# design.net
KiCad netlist of a schematic drawn in Altium Designer
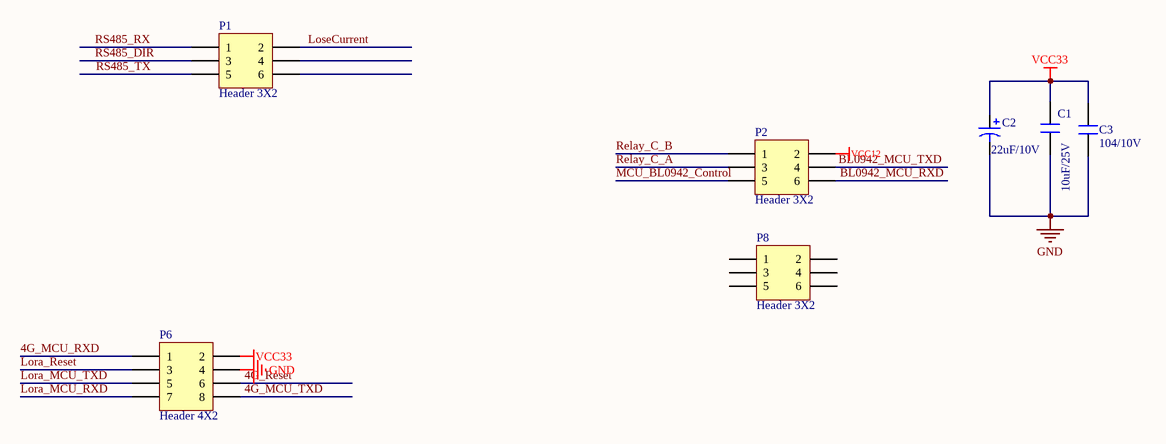
[diagram p0: 连接.SchDoc]

(export (version "E")
  (design (tool "Eeschema 10.0.6"))
  (components
    (comp (ref "C1") (value "10uF/25V") (footprint "0603R") (libsource (lib "ES_Schematic") (part "CAP")))
    (comp (ref "C2")
      (value "22uF/10V")
      (footprint "0805R")
      (description "Polarized Capacitor (Radial)")
      (fields (field (name "PUBLISHER") "Altium Limited"))
      (libsource (lib "Miscellaneous Devices") (part "Cap Pol1"))
    )
    (comp (ref "C3") (value "104/10V") (footprint "0603R") (libsource (lib "ES_Schematic") (part "CAP_1")))
    (comp (ref "P1")
      (value "Header 3X2")
      (footprint "CONN-SMD_5BME8-08872-203-W0")
      (description "Header, 3-Pin, Dual row")
      (fields (field (name "PUBLISHER") "Altium Limited"))
      (libsource (lib "Miscellaneous Connectors") (part "Header 3X2"))
    )
    (comp (ref "P2")
      (value "Header 3X2")
      (footprint "CONN-SMD_5BME8-08872-203-W0")
      (description "Header, 3-Pin, Dual row")
      (fields (field (name "PUBLISHER") "Altium Limited"))
      (libsource (lib "Miscellaneous Connectors") (part "Header 3X2"))
    )
    (comp (ref "P6")
      (value "Header 4X2")
      (footprint "CONN-SMD_5BME8-08872-204-W0")
      (description "Header, 4-Pin, Dual row")
      (fields (field (name "PUBLISHER") "Altium Limited"))
      (libsource (lib "Miscellaneous Connectors") (part "Header 4X2"))
    )
    (comp (ref "P8")
      (value "Header 3X2")
      (footprint "CONN-SMD_5BME8-08872-203-W0")
      (description "Header, 3-Pin, Dual row")
      (fields (field (name "PUBLISHER") "Altium Limited"))
      (libsource (lib "Miscellaneous Connectors") (part "Header 3X2"))
    )
  )
  (nets
    (net (code "1") (name "/4G_MCU_RXD") (class "Default")
      (node (ref "P6") (pin "1") (pinfunction "1_1") (pintype "passive"))
    )
    (net (code "2") (name "/4G_MCU_TXD") (class "Default")
      (node (ref "P6") (pin "8") (pinfunction "8_8") (pintype "passive"))
    )
    (net (code "3") (name "/4G_Reset") (class "Default")
      (node (ref "P6") (pin "6") (pinfunction "6_6") (pintype "passive"))
    )
    (net (code "4") (name "/BL0942_MCU_RXD") (class "Default")
      (node (ref "P2") (pin "6") (pinfunction "6_6") (pintype "passive"))
    )
    (net (code "5") (name "/BL0942_MCU_TXD") (class "Default")
      (node (ref "P2") (pin "4") (pinfunction "4_4") (pintype "passive"))
    )
    (net (code "6") (name "/Lora_MCU_RXD") (class "Default")
      (node (ref "P6") (pin "7") (pinfunction "7_7") (pintype "passive"))
    )
    (net (code "7") (name "/Lora_MCU_TXD") (class "Default")
      (node (ref "P6") (pin "5") (pinfunction "5_5") (pintype "passive"))
    )
    (net (code "8") (name "/Lora_Reset") (class "Default")
      (node (ref "P6") (pin "3") (pinfunction "3_3") (pintype "passive"))
    )
    (net (code "9") (name "/LoseCurrent") (class "Default")
      (node (ref "P1") (pin "2") (pinfunction "2_2") (pintype "passive"))
    )
    (net (code "10") (name "/MCU_BL0942_Control") (class "Default")
      (node (ref "P2") (pin "5") (pinfunction "5_5") (pintype "passive"))
    )
    (net (code "11") (name "/RS485_DIR") (class "Default")
      (node (ref "P1") (pin "3") (pinfunction "3_3") (pintype "passive"))
    )
    (net (code "12") (name "/RS485_RX") (class "Default")
      (node (ref "P1") (pin "1") (pinfunction "1_1") (pintype "passive"))
    )
    (net (code "13") (name "/RS485_TX") (class "Default")
      (node (ref "P1") (pin "5") (pinfunction "5_5") (pintype "passive"))
    )
    (net (code "14") (name "/Relay_C_A") (class "Default")
      (node (ref "P2") (pin "3") (pinfunction "3_3") (pintype "passive"))
    )
    (net (code "15") (name "/Relay_C_B") (class "Default")
      (node (ref "P2") (pin "1") (pinfunction "1_1") (pintype "passive"))
    )
    (net (code "16") (name "GND") (class "Default")
      (node (ref "C1") (pin "1") (pinfunction "1_1") (pintype "passive"))
      (node (ref "C2") (pin "2") (pinfunction "2_2") (pintype "passive"))
      (node (ref "C3") (pin "1") (pinfunction "1_1") (pintype "passive"))
      (node (ref "P6") (pin "4") (pinfunction "4_4") (pintype "passive"))
    )
    (net (code "17") (name "VCC12") (class "Default")
      (node (ref "P2") (pin "2") (pinfunction "2_2") (pintype "passive"))
    )
    (net (code "18") (name "VCC33") (class "Default")
      (node (ref "C1") (pin "2") (pinfunction "2_2") (pintype "passive"))
      (node (ref "C2") (pin "1") (pinfunction "1_1") (pintype "passive"))
      (node (ref "C3") (pin "2") (pinfunction "2_2") (pintype "passive"))
      (node (ref "P6") (pin "2") (pinfunction "2_2") (pintype "passive"))
    )
    (net (code "19") (name "unconnected-(P1-Pad4)") (class "Default")
      (node (ref "P1") (pin "4") (pinfunction "4_4") (pintype "passive"))
    )
    (net (code "20") (name "unconnected-(P1-Pad6)") (class "Default")
      (node (ref "P1") (pin "6") (pinfunction "6_6") (pintype "passive"))
    )
    (net (code "21") (name "unconnected-(P8-Pad1)") (class "Default")
      (node (ref "P8") (pin "1") (pinfunction "1_1") (pintype "passive"))
    )
    (net (code "22") (name "unconnected-(P8-Pad2)") (class "Default")
      (node (ref "P8") (pin "2") (pinfunction "2_2") (pintype "passive"))
    )
    (net (code "23") (name "unconnected-(P8-Pad3)") (class "Default")
      (node (ref "P8") (pin "3") (pinfunction "3_3") (pintype "passive"))
    )
    (net (code "24") (name "unconnected-(P8-Pad4)") (class "Default")
      (node (ref "P8") (pin "4") (pinfunction "4_4") (pintype "passive"))
    )
    (net (code "25") (name "unconnected-(P8-Pad5)") (class "Default")
      (node (ref "P8") (pin "5") (pinfunction "5_5") (pintype "passive"))
    )
    (net (code "26") (name "unconnected-(P8-Pad6)") (class "Default")
      (node (ref "P8") (pin "6") (pinfunction "6_6") (pintype "passive"))
    )
  )
)
